# MOTOR_DRIVER.net
KiCad netlist of a schematic drawn in EAGLE
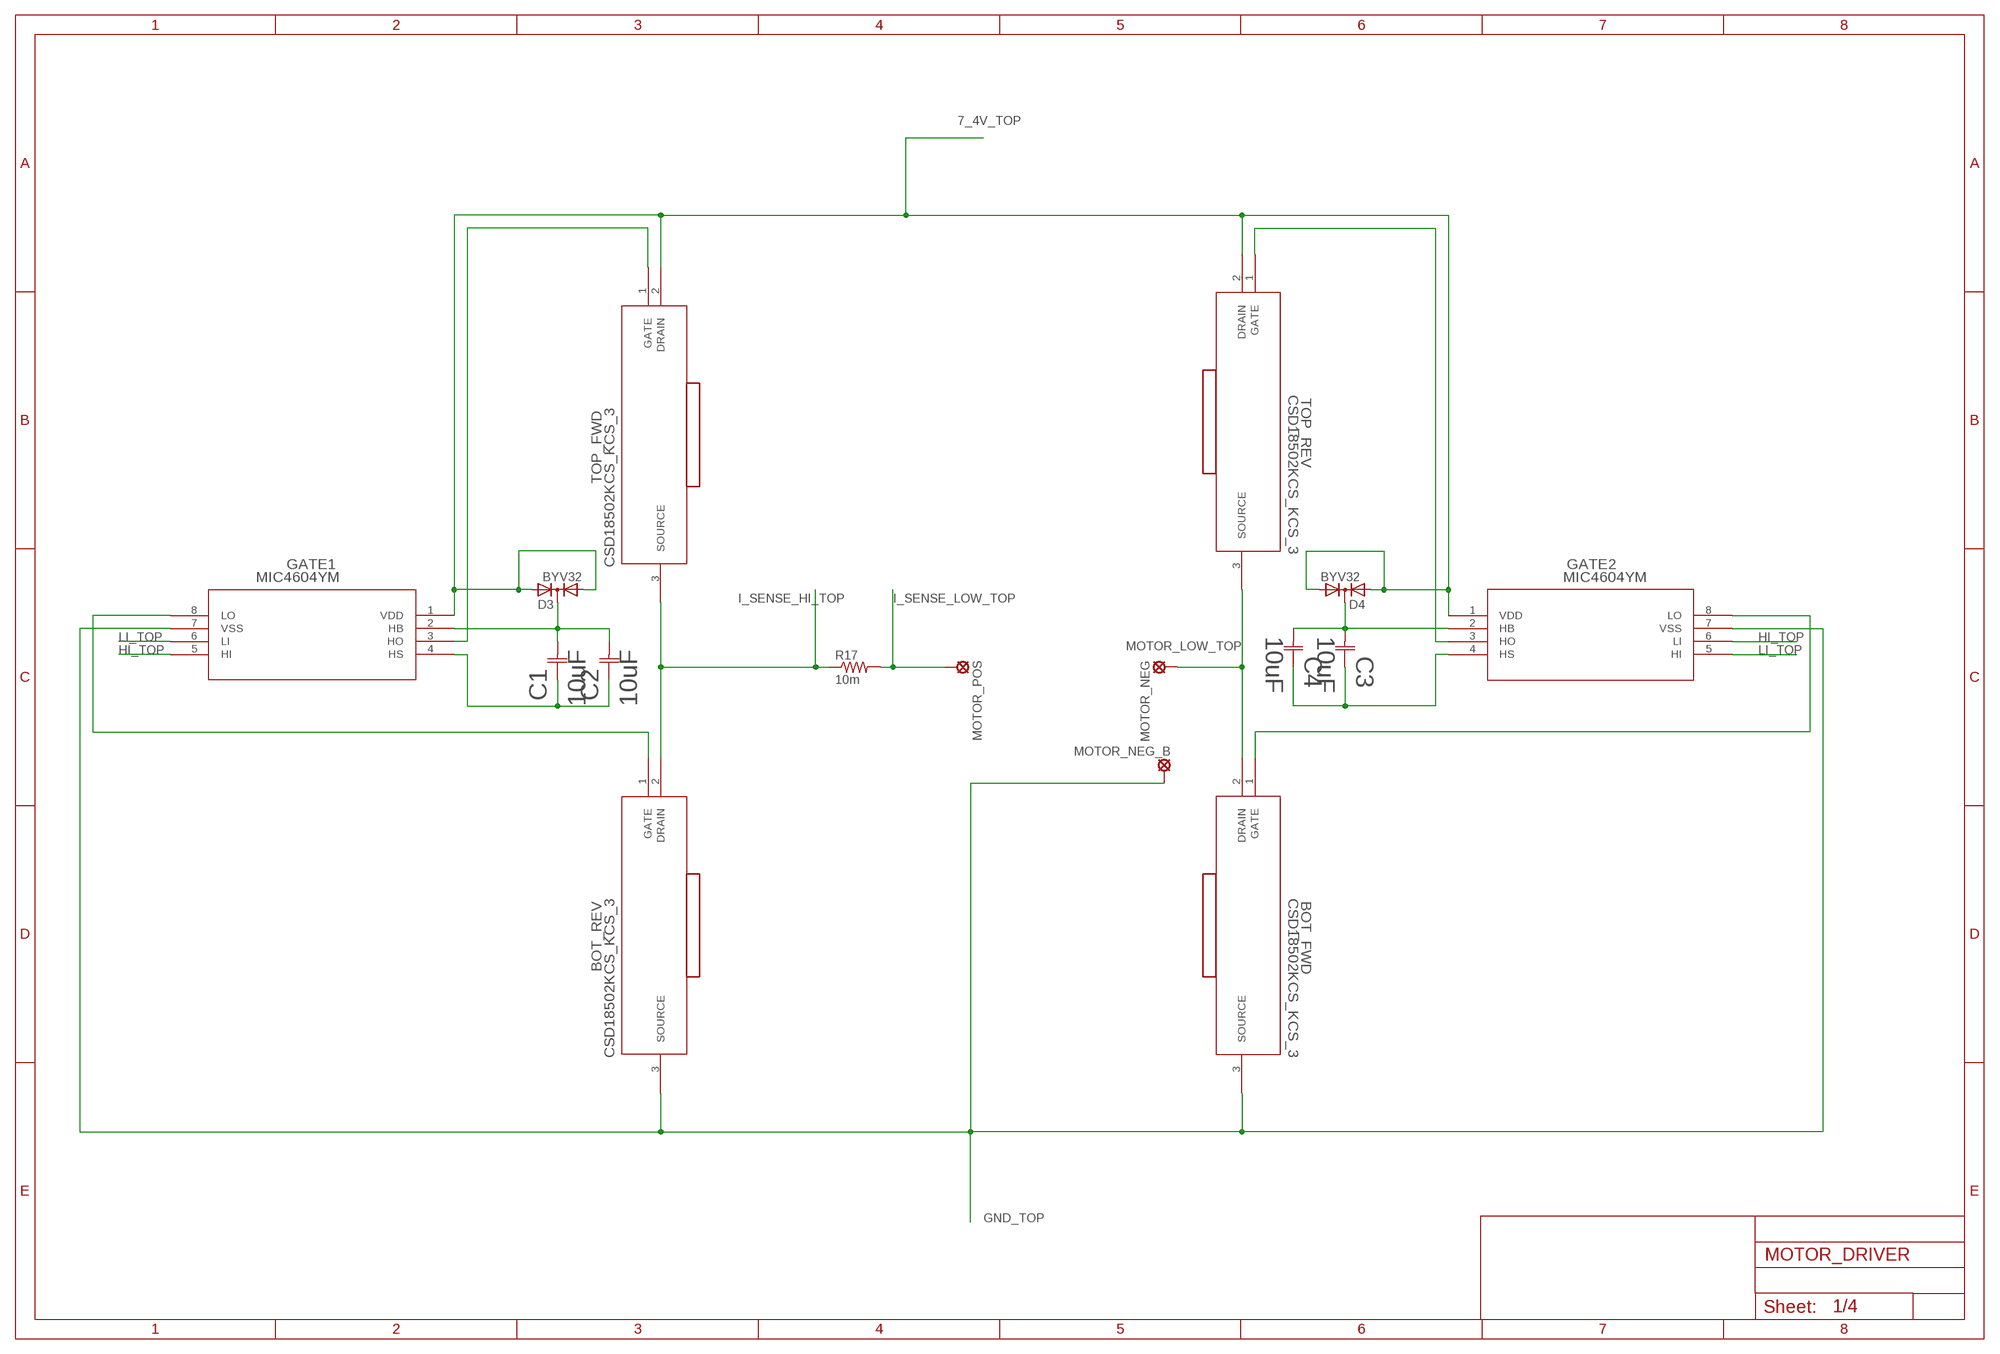
[diagram p0: schematic, sheet 1]
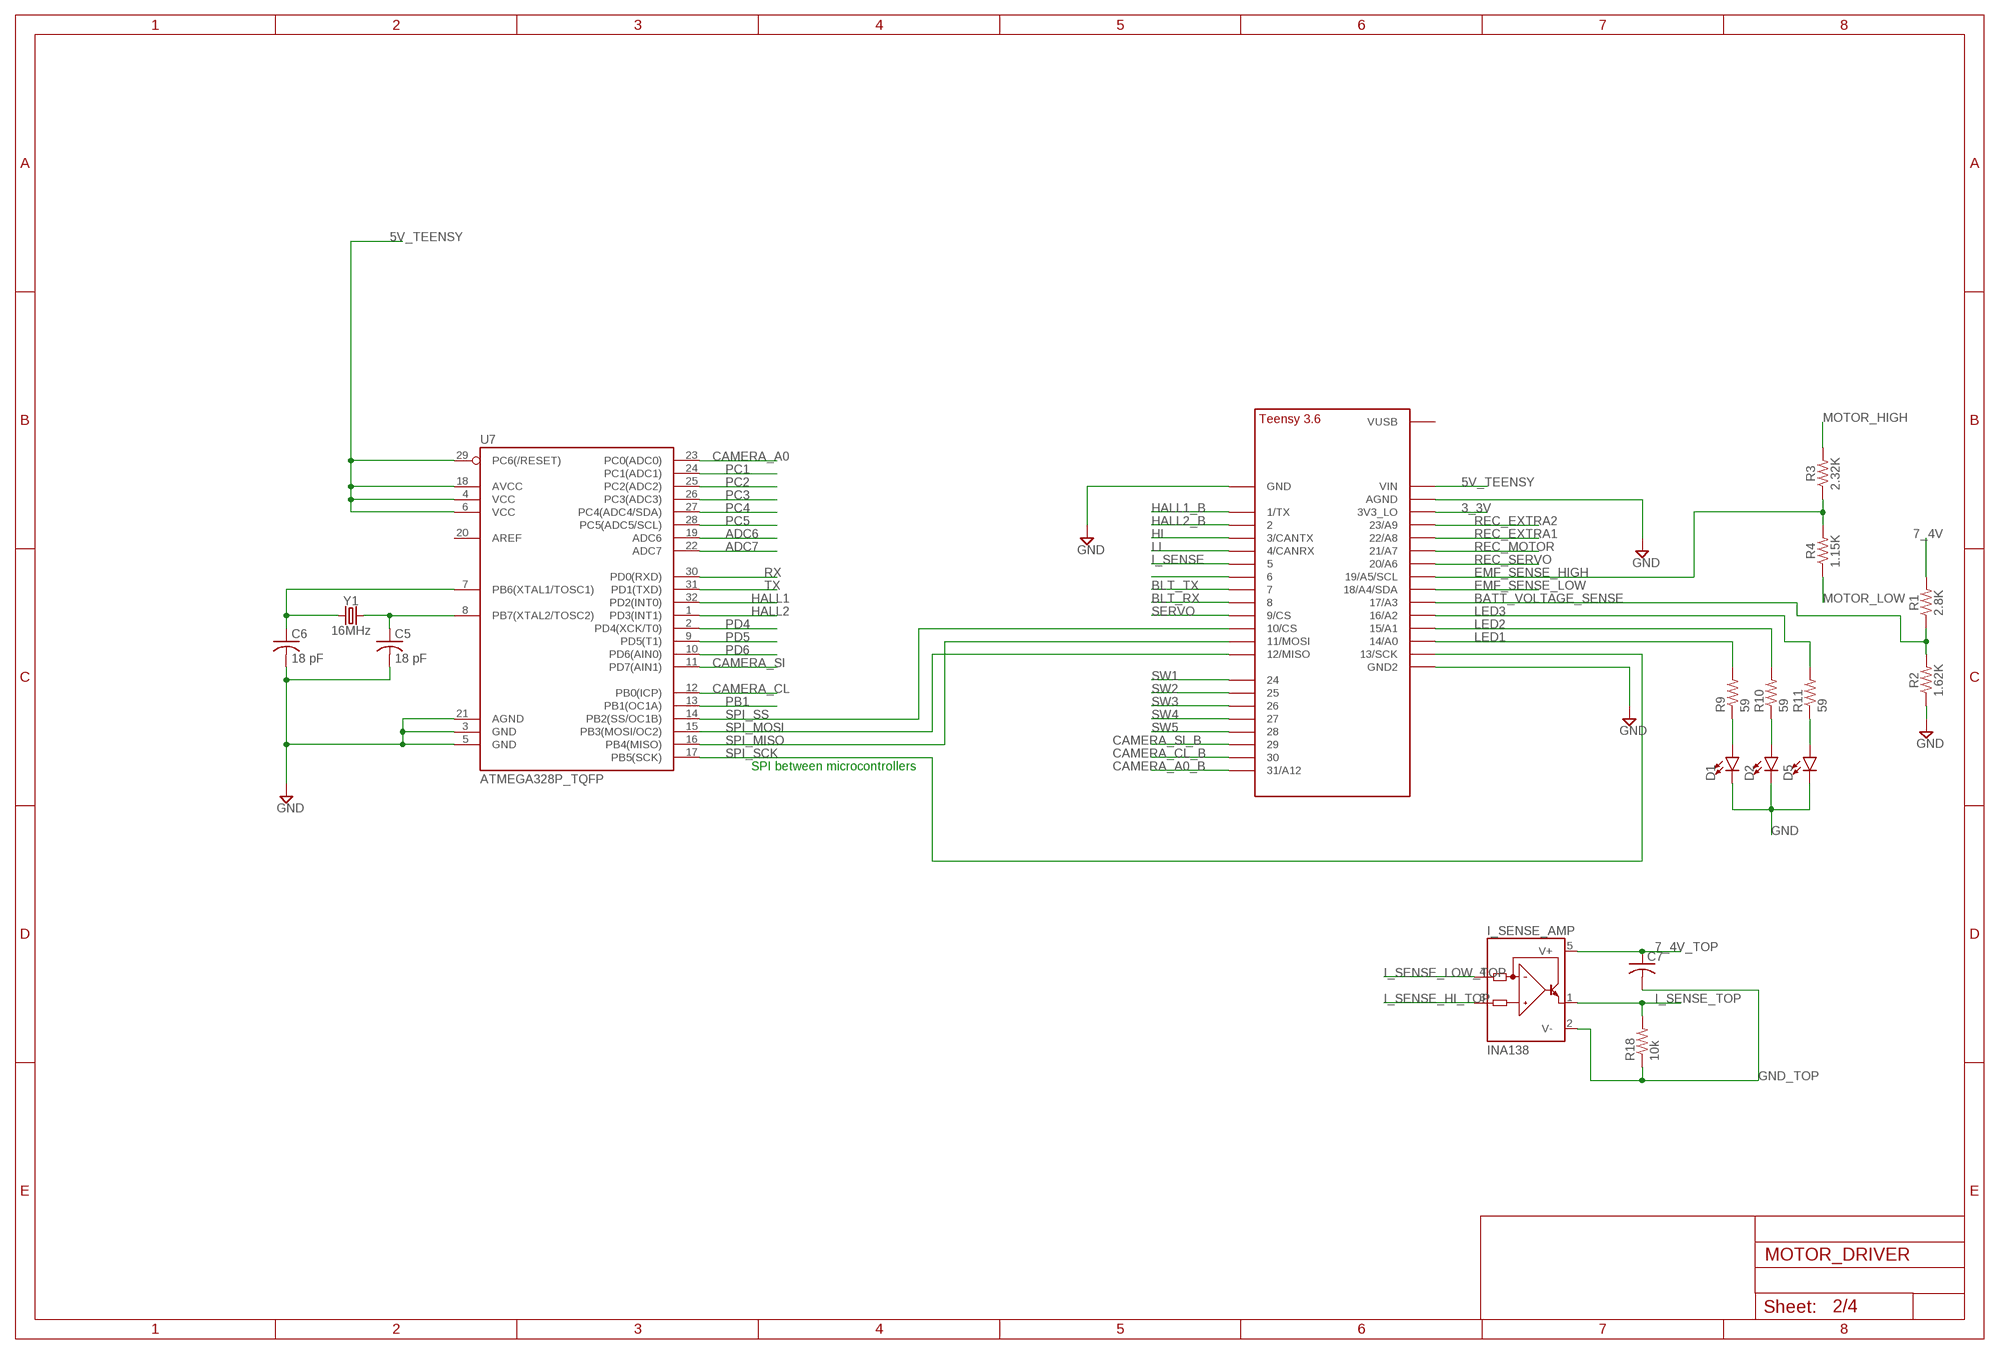
[diagram p1: schematic, sheet 2]
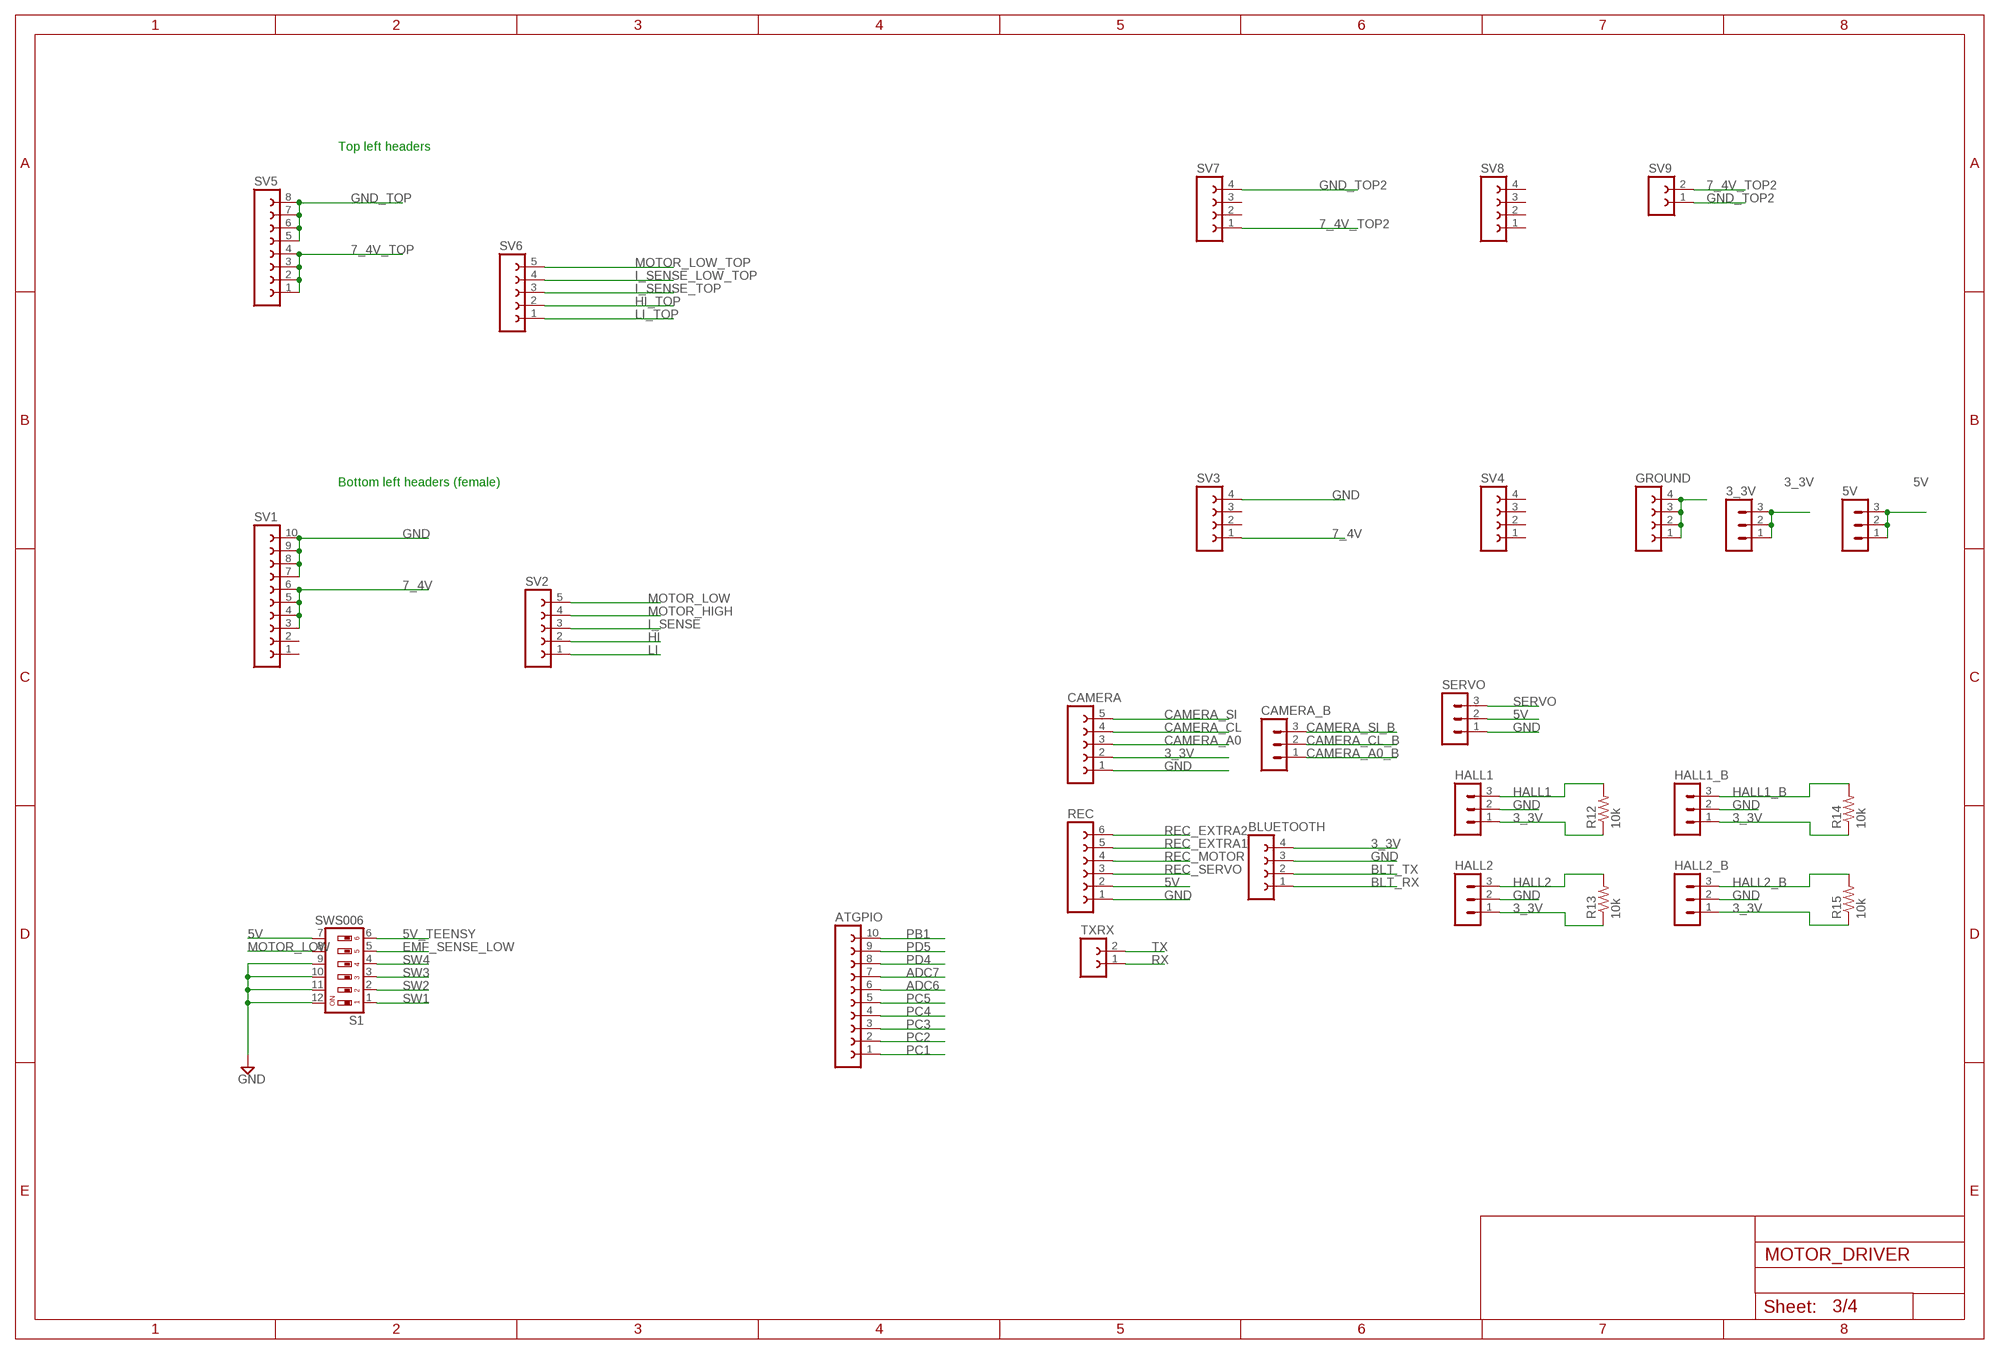
[diagram p2: schematic, sheet 3]
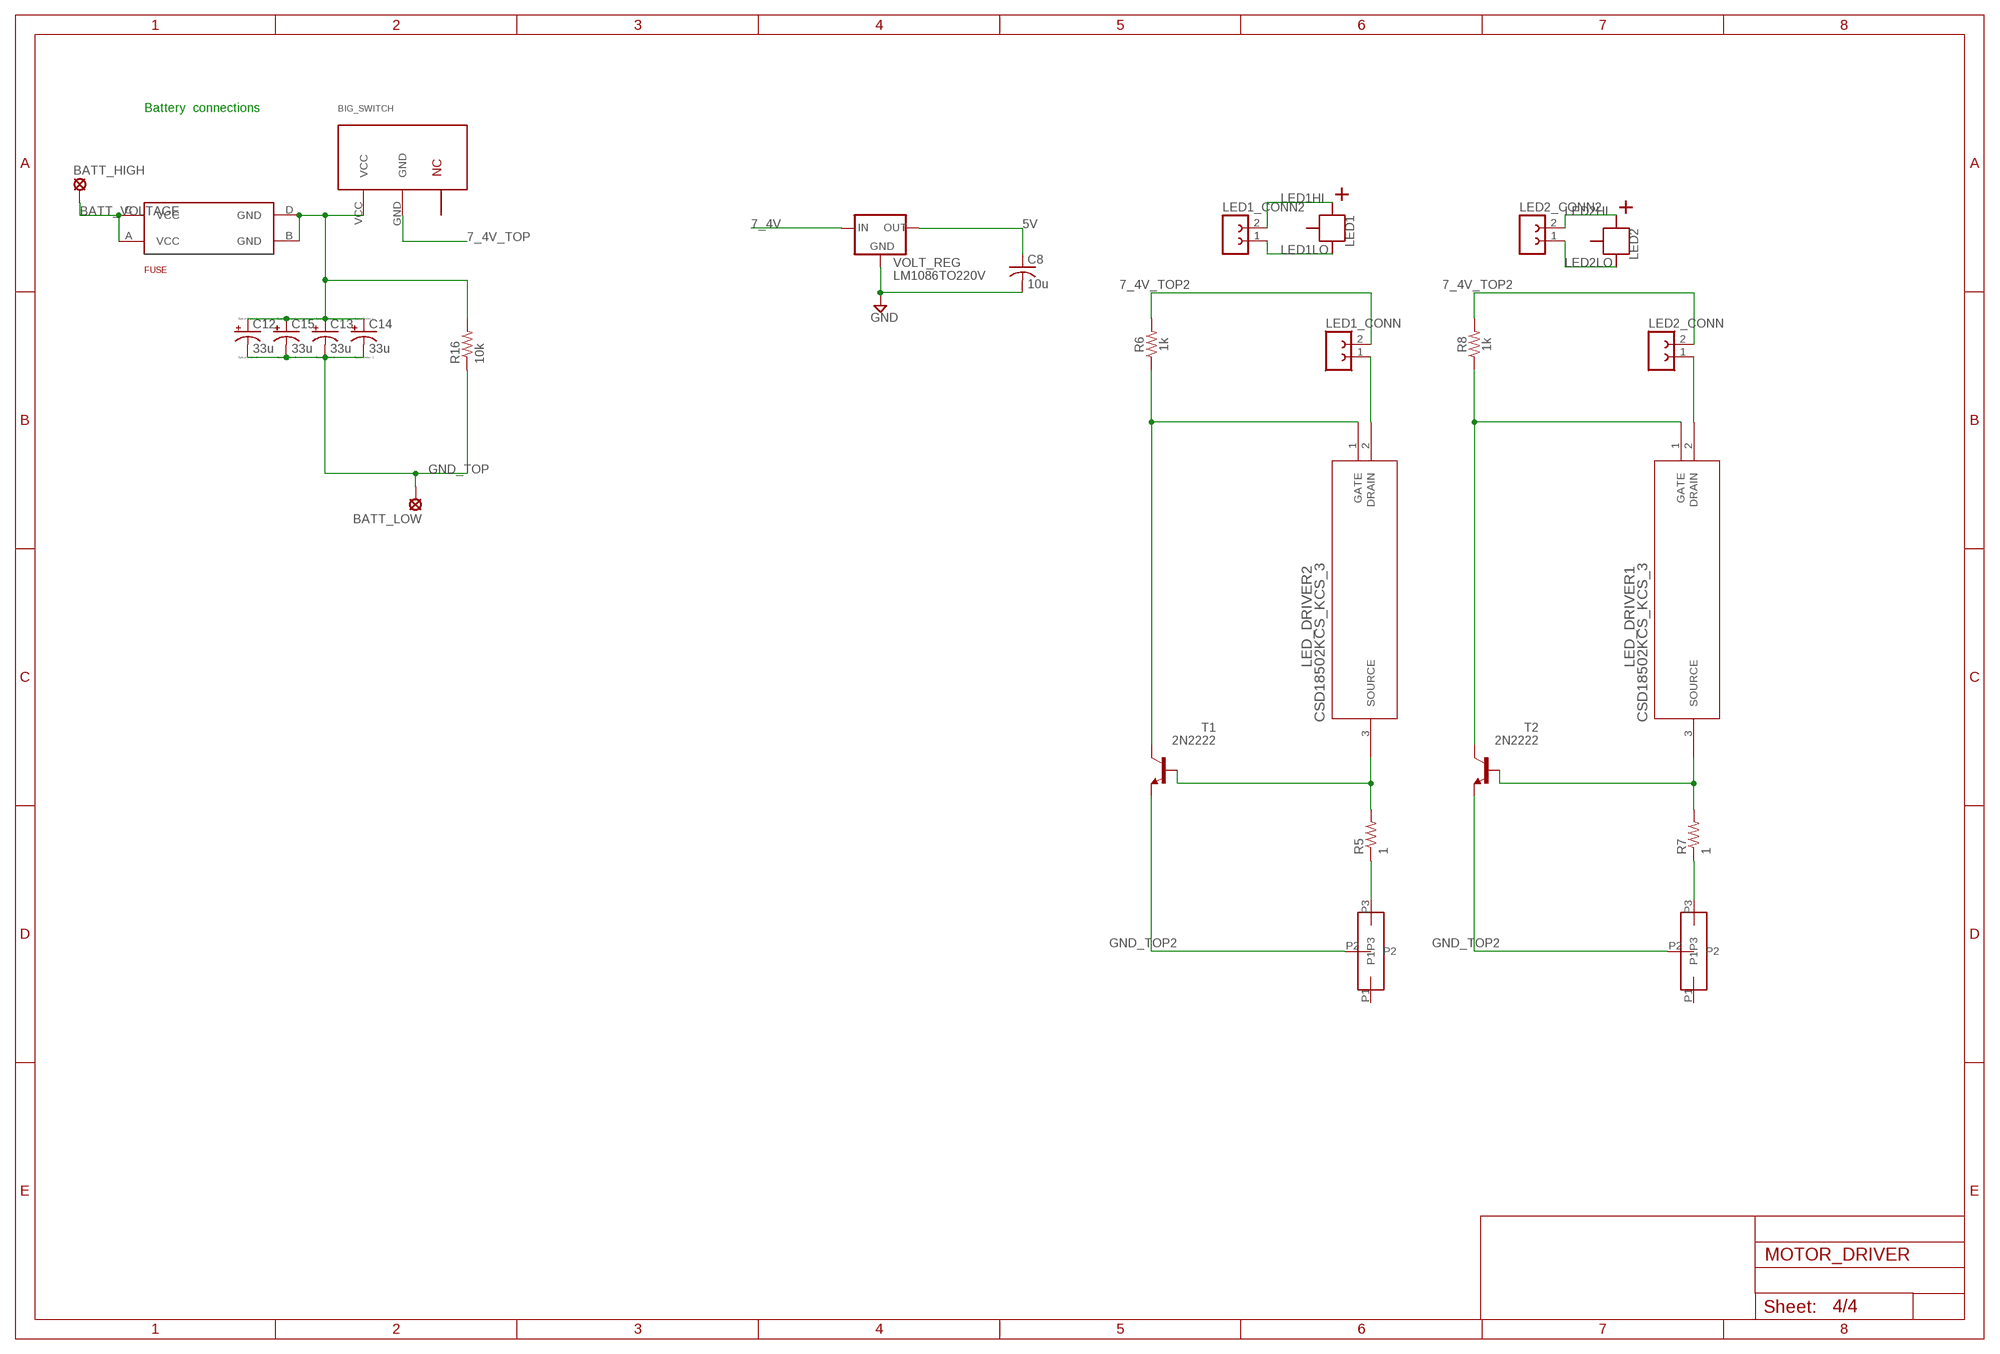
[diagram p3: schematic, sheet 4]

(export (version "E")
  (design (tool "Eeschema 10.0.6"))
  (components
    (comp (ref "BATT_HIGH")
      (value "SE14")
      (footprint "eagle-import:SE14")
      (libsource (lib "eagle-import") (part "SE14"))
    )
    (comp (ref "BATT_LOW")
      (value "SE14")
      (footprint "eagle-import:SE14")
      (libsource (lib "eagle-import") (part "SE14"))
    )
    (comp (ref "BIG_SWITCH")
      (value "BIGSWITCH")
      (footprint "eagle-import:BIGSWITCH")
      (fields
        (field (name "DIGIKEY_PART_NUMBER") "CW106-ND")
        (field (name "MANUFACTURER") "CW Industries")
        (field (name "MANUFACTURER_PART_NUMBER") "GRB238B801BR1")
      )
      (libsource (lib "eagle-import") (part "BIGSWITCH"))
    )
    (comp (ref "C8")
      (value "10u")
      (footprint "eagle-import:C0805")
      (libsource (lib "eagle-import") (part "C-USC0805"))
    )
    (comp (ref "C12")
      (value "33u")
      (footprint "eagle-import:153CLV-1010")
      (libsource (lib "eagle-import") (part "CPOL-US153CLV-1010"))
    )
    (comp (ref "C13")
      (value "33u")
      (footprint "eagle-import:153CLV-1010")
      (libsource (lib "eagle-import") (part "CPOL-US153CLV-1010"))
    )
    (comp (ref "C14")
      (value "33u")
      (footprint "eagle-import:153CLV-1010")
      (libsource (lib "eagle-import") (part "CPOL-US153CLV-1010"))
    )
    (comp (ref "C15")
      (value "33u")
      (footprint "eagle-import:153CLV-1010")
      (libsource (lib "eagle-import") (part "CPOL-US153CLV-1010"))
    )
    (comp (ref "FUSE")
      (value "FUSEHOLDER3588")
      (footprint "eagle-import:FUSEHOLDER3588")
      (fields
        (field (name "DIGIKEY_PART_NUMBER") "F4989-ND")
        (field (name "MANUFACTURER") "Littelfuse Inc.")
        (field (name "MANUFACTURER_PART_NUMBER") "0891010.NXS")
      )
      (libsource (lib "eagle-import") (part "FUSEHOLDER3588"))
    )
    (comp (ref "LED1")
      (value "CREE_XP")
      (footprint "eagle-import:XP")
      (libsource (lib "eagle-import") (part "CREE_XP"))
    )
    (comp (ref "LED1_CONN")
      (value "FE02-1")
      (footprint "eagle-import:FE02-1")
      (libsource (lib "eagle-import") (part "FE02-1"))
    )
    (comp (ref "LED1_CONN2")
      (value "FE02-1")
      (footprint "eagle-import:FE02-1")
      (libsource (lib "eagle-import") (part "FE02-1"))
    )
    (comp (ref "LED2")
      (value "CREE_XP")
      (footprint "eagle-import:XP")
      (libsource (lib "eagle-import") (part "CREE_XP"))
    )
    (comp (ref "LED2_CONN")
      (value "FE02-1")
      (footprint "eagle-import:FE02-1")
      (libsource (lib "eagle-import") (part "FE02-1"))
    )
    (comp (ref "LED2_CONN2")
      (value "FE02-1")
      (footprint "eagle-import:FE02-1")
      (libsource (lib "eagle-import") (part "FE02-1"))
    )
    (comp (ref "LED_DRIVER1")
      (value "CSD18502KCS_KCS_3")
      (footprint "eagle-import:KCS3")
      (fields
        (field (name "DIGIKEY_PART_NUMBER") "296-35013-ND")
        (field (name "MANUFACTURER") "Texas Instruments")
        (field (name "MANUFACTURER_PART_NUMBER") "CSD18533KCS")
      )
      (libsource (lib "eagle-import") (part "CSD18502KCS_KCS_3"))
    )
    (comp (ref "LED_DRIVER2")
      (value "CSD18502KCS_KCS_3")
      (footprint "eagle-import:KCS3")
      (fields
        (field (name "DIGIKEY_PART_NUMBER") "296-35013-ND")
        (field (name "MANUFACTURER") "Texas Instruments")
        (field (name "MANUFACTURER_PART_NUMBER") "CSD18533KCS")
      )
      (libsource (lib "eagle-import") (part "CSD18502KCS_KCS_3"))
    )
    (comp (ref "R5")
      (value "1")
      (footprint "eagle-import:R2512")
      (libsource (lib "eagle-import") (part "R-US_R2512"))
    )
    (comp (ref "R6")
      (value "1k")
      (footprint "eagle-import:AXIAL-0.3")
      (libsource (lib "eagle-import") (part "1KOHM-HORIZ-1/4W-1%"))
    )
    (comp (ref "R7")
      (value "1")
      (footprint "eagle-import:R2512")
      (libsource (lib "eagle-import") (part "R-US_R2512"))
    )
    (comp (ref "R8")
      (value "1k")
      (footprint "eagle-import:AXIAL-0.3")
      (libsource (lib "eagle-import") (part "1KOHM-HORIZ-1/4W-1%"))
    )
    (comp (ref "R16")
      (value "10k")
      (footprint "eagle-import:R0603")
      (libsource (lib "eagle-import") (part "resistor_R-US_R0603"))
    )
    (comp (ref "T1")
      (value "2N2222")
      (footprint "eagle-import:TO18")
      (libsource (lib "eagle-import") (part "2N2222"))
    )
    (comp (ref "T2")
      (value "2N2222")
      (footprint "eagle-import:TO18")
      (libsource (lib "eagle-import") (part "2N2222"))
    )
    (comp (ref "U$3")
      (value "POT")
      (footprint "eagle-import:POT")
      (libsource (lib "eagle-import") (part "POT"))
    )
    (comp (ref "U$7")
      (value "POT")
      (footprint "eagle-import:POT")
      (libsource (lib "eagle-import") (part "POT"))
    )
    (comp (ref "VOLT_REG")
      (value "LM1086TO220V")
      (footprint "eagle-import:TO220S")
      (fields
        (field (name "DIGIKEY_PART_NUMBER") "LM1086IT-5.0/NOPB-ND")
        (field (name "MANUFACTURER") "Texas Instruments")
        (field (name "MANUFACTURER_PART_NUMBER") "LM1086IT-5.0/NOPB")
      )
      (libsource (lib "eagle-import") (part "LM1086TO220V"))
    )
    (comp (ref "3_3V")
      (value "MA03-1")
      (footprint "eagle-import:MA03-1")
      (libsource (lib "eagle-import") (part "MA03-1"))
    )
    (comp (ref "5V")
      (value "MA03-1")
      (footprint "eagle-import:MA03-1")
      (libsource (lib "eagle-import") (part "MA03-1"))
    )
    (comp (ref "ATGPIO")
      (value "FE10-1")
      (footprint "eagle-import:FE10")
      (libsource (lib "eagle-import") (part "FE10-1"))
    )
    (comp (ref "BLUETOOTH")
      (value "FE04-1")
      (footprint "eagle-import:FE04-1")
      (fields
        (field (name "MANUFACTURER") "HC Information Technology")
        (field (name "MANUFACTURER_PART_NUMBER") "HC-06")
      )
      (libsource (lib "eagle-import") (part "FE04-1"))
    )
    (comp (ref "CAMERA")
      (value "FE05-1")
      (footprint "eagle-import:FE05-1")
      (fields
        (field (name "DIGIKEY_PART_NUMBER") "28317-ND")
        (field (name "MANUFACTURER") "Parallax")
        (field (name "MANUFACTURER_PART_NUMBER") "28317")
      )
      (libsource (lib "eagle-import") (part "FE05-1"))
    )
    (comp (ref "CAMERA_B")
      (value "MA03-1")
      (footprint "eagle-import:MA03-1")
      (fields
        (field (name "DIGIKEY_PART_NUMBER") "28317-ND")
        (field (name "MANUFACTURER") "Parallax")
        (field (name "MANUFACTURER_PART_NUMBER") "28317")
      )
      (libsource (lib "eagle-import") (part "MA03-1"))
    )
    (comp (ref "GROUND")
      (value "FE04-1")
      (footprint "eagle-import:FE04-1")
      (libsource (lib "eagle-import") (part "FE04-1"))
    )
    (comp (ref "HALL1")
      (value "MA03-1")
      (footprint "eagle-import:MA03-1")
      (fields
        (field (name "DIGIKEY_PART_NUMBER") "US1881LUA-AAA-000-BU-ND")
        (field (name "MANUFACTURER") "Melexis Technologies NV")
        (field (name "MANUFACTURER_PART_NUMBER") "US1881LUA-AAA-000-BU")
      )
      (libsource (lib "eagle-import") (part "MA03-1"))
    )
    (comp (ref "HALL1_B")
      (value "MA03-1")
      (footprint "eagle-import:MA03-1")
      (fields
        (field (name "DIGIKEY_PART_NUMBER") "US1881LUA-AAA-000-BU-ND")
        (field (name "MANUFACTURER") "Melexis Technologies NV")
        (field (name "MANUFACTURER_PART_NUMBER") "US1881LUA-AAA-000-BU")
      )
      (libsource (lib "eagle-import") (part "MA03-1"))
    )
    (comp (ref "HALL2")
      (value "MA03-1")
      (footprint "eagle-import:MA03-1")
      (fields
        (field (name "DIGIKEY_PART_NUMBER") "US1881LUA-AAA-000-BU-ND")
        (field (name "MANUFACTURER") "Melexis Technologies NV")
        (field (name "MANUFACTURER_PART_NUMBER") "US1881LUA-AAA-000-BU")
      )
      (libsource (lib "eagle-import") (part "MA03-1"))
    )
    (comp (ref "HALL2_B")
      (value "MA03-1")
      (footprint "eagle-import:MA03-1")
      (fields
        (field (name "DIGIKEY_PART_NUMBER") "US1881LUA-AAA-000-BU-ND")
        (field (name "MANUFACTURER") "Melexis Technologies NV")
        (field (name "MANUFACTURER_PART_NUMBER") "US1881LUA-AAA-000-BU")
      )
      (libsource (lib "eagle-import") (part "MA03-1"))
    )
    (comp (ref "R12")
      (value "10k")
      (footprint "eagle-import:R0603")
      (libsource (lib "eagle-import") (part "resistor_R-US_R0603"))
    )
    (comp (ref "R13")
      (value "10k")
      (footprint "eagle-import:R0603")
      (libsource (lib "eagle-import") (part "resistor_R-US_R0603"))
    )
    (comp (ref "R14")
      (value "10k")
      (footprint "eagle-import:R0603")
      (libsource (lib "eagle-import") (part "resistor_R-US_R0603"))
    )
    (comp (ref "R15")
      (value "10k")
      (footprint "eagle-import:R0603")
      (libsource (lib "eagle-import") (part "resistor_R-US_R0603"))
    )
    (comp (ref "REC")
      (value "FE06-1")
      (footprint "eagle-import:FE06")
      (libsource (lib "eagle-import") (part "FE06-1"))
    )
    (comp (ref "S1")
      (value "SWS006")
      (footprint "eagle-import:SMS-006")
      (fields
        (field (name "DIGIKEY_PART_NUMBER") "CT2196MST-ND")
        (field (name "MANUFACTURER") "CTS Electrocomponents")
        (field (name "MANUFACTURER_PART_NUMBER") "219-6MST")
      )
      (libsource (lib "eagle-import") (part "SWS006"))
    )
    (comp (ref "SERVO")
      (value "MA03-1")
      (footprint "eagle-import:MA03-1")
      (fields (field (name "MANUFACTURER") "TrackStar") (field (name "MANUFACTURER_PART_NUMBER") "TS-P12S"))
      (libsource (lib "eagle-import") (part "MA03-1"))
    )
    (comp (ref "SV1")
      (value "FE10-1")
      (footprint "eagle-import:FE10")
      (libsource (lib "eagle-import") (part "FE10-1"))
    )
    (comp (ref "SV2")
      (value "FE05-1")
      (footprint "eagle-import:FE05-1")
      (libsource (lib "eagle-import") (part "FE05-1"))
    )
    (comp (ref "SV3")
      (value "FE04-1")
      (footprint "eagle-import:FE04-1")
      (libsource (lib "eagle-import") (part "FE04-1"))
    )
    (comp (ref "SV4")
      (value "FE04-1")
      (footprint "eagle-import:FE04-1")
      (libsource (lib "eagle-import") (part "FE04-1"))
    )
    (comp (ref "SV5")
      (value "FE08-1")
      (footprint "eagle-import:FE08")
      (libsource (lib "eagle-import") (part "FE08-1"))
    )
    (comp (ref "SV6")
      (value "FE05-1")
      (footprint "eagle-import:FE05-1")
      (libsource (lib "eagle-import") (part "FE05-1"))
    )
    (comp (ref "SV7")
      (value "FE04-1")
      (footprint "eagle-import:FE04-1")
      (libsource (lib "eagle-import") (part "FE04-1"))
    )
    (comp (ref "SV8")
      (value "FE04-1")
      (footprint "eagle-import:FE04-1")
      (libsource (lib "eagle-import") (part "FE04-1"))
    )
    (comp (ref "SV9")
      (value "FE02-1")
      (footprint "eagle-import:FE02-1")
      (libsource (lib "eagle-import") (part "FE02-1"))
    )
    (comp (ref "TXRX")
      (value "FE02-1")
      (footprint "eagle-import:FE02-1")
      (libsource (lib "eagle-import") (part "FE02-1"))
    )
    (comp (ref "BOT_FWD")
      (value "CSD18502KCS_KCS_3")
      (footprint "eagle-import:KCS3")
      (fields
        (field (name "DIGIKEY_PART_NUMBER") "296-35013-ND")
        (field (name "MANUFACTURER") "Texas Instruments")
        (field (name "MANUFACTURER_PART_NUMBER") "CSD18533KCS")
      )
      (libsource (lib "eagle-import") (part "CSD18502KCS_KCS_3"))
    )
    (comp (ref "BOT_REV")
      (value "CSD18502KCS_KCS_3")
      (footprint "eagle-import:KCS3")
      (fields
        (field (name "DIGIKEY_PART_NUMBER") "296-35013-ND")
        (field (name "MANUFACTURER") "Texas Instruments")
        (field (name "MANUFACTURER_PART_NUMBER") "CSD18533KCS")
      )
      (libsource (lib "eagle-import") (part "CSD18502KCS_KCS_3"))
    )
    (comp (ref "C1")
      (value "10uF")
      (footprint "eagle-import:CAP_EEE_B")
      (fields (field (name "MANUFACTURER_PART_NUMBER") "EEE1VA100WR"))
      (libsource (lib "eagle-import") (part "EEE1VA100WR"))
    )
    (comp (ref "C2")
      (value "10uF")
      (footprint "eagle-import:CAP_EEE_B")
      (fields (field (name "MANUFACTURER_PART_NUMBER") "EEE1VA100WR"))
      (libsource (lib "eagle-import") (part "EEE1VA100WR"))
    )
    (comp (ref "C3")
      (value "10uF")
      (footprint "eagle-import:CAP_EEE_B")
      (fields (field (name "MANUFACTURER_PART_NUMBER") "EEE1VA100WR"))
      (libsource (lib "eagle-import") (part "EEE1VA100WR"))
    )
    (comp (ref "C4")
      (value "10uF")
      (footprint "eagle-import:CAP_EEE_B")
      (fields (field (name "MANUFACTURER_PART_NUMBER") "EEE1VA100WR"))
      (libsource (lib "eagle-import") (part "EEE1VA100WR"))
    )
    (comp (ref "D3")
      (value "BYV32")
      (footprint "eagle-import:TO220ABS")
      (libsource (lib "eagle-import") (part "BYV32"))
    )
    (comp (ref "D4")
      (value "BYV32")
      (footprint "eagle-import:TO220ABS")
      (libsource (lib "eagle-import") (part "BYV32"))
    )
    (comp (ref "GATE1")
      (value "MIC4604YM")
      (footprint "eagle-import:SOIC-8_M")
      (fields
        (field (name "DIGIKEY_PART_NUMBER") "576-4395-1-ND")
        (field (name "MANUFACTURER") "Microchip")
        (field (name "MANUFACTURER_PART_NUMBER") "MIC4604YM-T5")
      )
      (libsource (lib "eagle-import") (part "MIC4604YM"))
    )
    (comp (ref "GATE2")
      (value "MIC4604YM")
      (footprint "eagle-import:SOIC-8_M")
      (fields
        (field (name "DIGIKEY_PART_NUMBER") "576-4395-1-ND")
        (field (name "MANUFACTURER") "Microchip")
        (field (name "MANUFACTURER_PART_NUMBER") "MIC4604YM-T5")
      )
      (libsource (lib "eagle-import") (part "MIC4604YM"))
    )
    (comp (ref "MOTOR_NEG")
      (value "SE14")
      (footprint "eagle-import:SE14")
      (libsource (lib "eagle-import") (part "SE14"))
    )
    (comp (ref "MOTOR_NEG_B")
      (value "SE14")
      (footprint "eagle-import:SE14")
      (libsource (lib "eagle-import") (part "SE14"))
    )
    (comp (ref "MOTOR_POS")
      (value "SE14")
      (footprint "eagle-import:SE14")
      (libsource (lib "eagle-import") (part "SE14"))
    )
    (comp (ref "R17")
      (value "10m")
      (footprint "eagle-import:R2512")
      (libsource (lib "eagle-import") (part "R-US_R2512"))
    )
    (comp (ref "TOP_FWD")
      (value "CSD18502KCS_KCS_3")
      (footprint "eagle-import:KCS3")
      (fields
        (field (name "DIGIKEY_PART_NUMBER") "296-35013-ND")
        (field (name "MANUFACTURER") "Texas Instruments")
        (field (name "MANUFACTURER_PART_NUMBER") "CSD18533KCS")
      )
      (libsource (lib "eagle-import") (part "CSD18502KCS_KCS_3"))
    )
    (comp (ref "TOP_REV")
      (value "CSD18502KCS_KCS_3")
      (footprint "eagle-import:KCS3")
      (fields
        (field (name "DIGIKEY_PART_NUMBER") "296-35013-ND")
        (field (name "MANUFACTURER") "Texas Instruments")
        (field (name "MANUFACTURER_PART_NUMBER") "CSD18533KCS")
      )
      (libsource (lib "eagle-import") (part "CSD18502KCS_KCS_3"))
    )
    (comp (ref "U$2")
      (value "HEATSINK")
      (footprint "eagle-import:HEATSINK")
      (fields
        (field (name "DIGIKEY_PART_NUMBER") "HS112-ND")
        (field (name "MANUFACTURER") "Aavid Thermalloy")
        (field (name "MANUFACTURER_PART_NUMBER") "507002B00000G")
      )
      (libsource (lib "eagle-import") (part "HEATSINK"))
    )
    (comp (ref "U$4")
      (value "HEATSINK")
      (footprint "eagle-import:HEATSINK")
      (fields
        (field (name "DIGIKEY_PART_NUMBER") "HS112-ND")
        (field (name "MANUFACTURER") "Aavid Thermalloy")
        (field (name "MANUFACTURER_PART_NUMBER") "507002B00000G")
      )
      (libsource (lib "eagle-import") (part "HEATSINK"))
    )
    (comp (ref "U$5")
      (value "HEATSINK")
      (footprint "eagle-import:HEATSINK")
      (fields
        (field (name "DIGIKEY_PART_NUMBER") "HS112-ND")
        (field (name "MANUFACTURER") "Aavid Thermalloy")
        (field (name "MANUFACTURER_PART_NUMBER") "507002B00000G")
      )
      (libsource (lib "eagle-import") (part "HEATSINK"))
    )
    (comp (ref "U$6")
      (value "HEATSINK")
      (footprint "eagle-import:HEATSINK")
      (fields
        (field (name "DIGIKEY_PART_NUMBER") "HS112-ND")
        (field (name "MANUFACTURER") "Aavid Thermalloy")
        (field (name "MANUFACTURER_PART_NUMBER") "507002B00000G")
      )
      (libsource (lib "eagle-import") (part "HEATSINK"))
    )
    (comp (ref "C5")
      (value "18 pF")
      (footprint "eagle-import:C0603")
      (libsource (lib "eagle-import") (part "C-USC0603"))
    )
    (comp (ref "C6")
      (value "18 pF")
      (footprint "eagle-import:C0603")
      (libsource (lib "eagle-import") (part "C-USC0603"))
    )
    (comp (ref "C7")
      (value "C-USC0603")
      (footprint "eagle-import:C0603")
      (libsource (lib "eagle-import") (part "resistor_C-USC0603"))
    )
    (comp (ref "D1")
      (value "LED0603")
      (footprint "eagle-import:LED-0603")
      (libsource (lib "eagle-import") (part "LED0603"))
    )
    (comp (ref "D2")
      (value "LED0603")
      (footprint "eagle-import:LED-0603")
      (libsource (lib "eagle-import") (part "LED0603"))
    )
    (comp (ref "D5")
      (value "LED0603")
      (footprint "eagle-import:LED-0603")
      (libsource (lib "eagle-import") (part "LED0603"))
    )
    (comp (ref "I_SENSE_AMP")
      (value "INA138")
      (footprint "eagle-import:SOT23-5")
      (fields
        (field (name "DIGIKEY_PART_NUMBER") "INA138NACT-ND")
        (field (name "MANUFACTURER") "Texas Instruments")
        (field (name "MANUFACTURER_PART_NUMBER") "INA138NA/250")
      )
      (libsource (lib "eagle-import") (part "INA138"))
    )
    (comp (ref "R1")
      (value "2.8K")
      (footprint "eagle-import:0805")
      (fields
        (field (name "DIGIKEY_PART_NUMBER") "311-2.80KCRCT-ND")
        (field (name "MANUFACTURER") "Yageo")
        (field (name "MANUFACTURER_PART_NUMBER") "RC0805FR-072K8L")
      )
      (libsource (lib "eagle-import") (part "0.3OHM-0805-1/8W-1%"))
    )
    (comp (ref "R2")
      (value "1.62K")
      (footprint "eagle-import:0805")
      (fields
        (field (name "DIGIKEY_PART_NUMBER") "311-1.62KCRCT-ND")
        (field (name "MANUFACTURER") "Yageo")
        (field (name "MANUFACTURER_PART_NUMBER") "RC0805FR-071K62L")
      )
      (libsource (lib "eagle-import") (part "0.3OHM-0805-1/8W-1%"))
    )
    (comp (ref "R3")
      (value "2.32K")
      (footprint "eagle-import:0805")
      (fields
        (field (name "DIGIKEY_PART_NUMBER") "311-2.32KCRCT-ND")
        (field (name "MANUFACTURER") "Yageo")
        (field (name "MANUFACTURER_PART_NUMBER") "RC0805FR-072K32L")
      )
      (libsource (lib "eagle-import") (part "0.3OHM-0805-1/8W-1%"))
    )
    (comp (ref "R4")
      (value "1.15K")
      (footprint "eagle-import:0805")
      (fields
        (field (name "DIGIKEY_PART_NUMBER") "311-1.15KCRCT-ND")
        (field (name "MANUFACTURER") "Yageo")
        (field (name "MANUFACTURER_PART_NUMBER") "RC0805FR-071K15L")
      )
      (libsource (lib "eagle-import") (part "0.3OHM-0805-1/8W-1%"))
    )
    (comp (ref "R9")
      (value "59")
      (footprint "eagle-import:R0805")
      (libsource (lib "eagle-import") (part "R-US_R0805"))
    )
    (comp (ref "R10")
      (value "59")
      (footprint "eagle-import:R0805")
      (libsource (lib "eagle-import") (part "R-US_R0805"))
    )
    (comp (ref "R11")
      (value "59")
      (footprint "eagle-import:R0805")
      (libsource (lib "eagle-import") (part "R-US_R0805"))
    )
    (comp (ref "R18")
      (value "10k")
      (footprint "eagle-import:R0603")
      (libsource (lib "eagle-import") (part "R-US_R0603"))
    )
    (comp (ref "U$1")
      (value "TEENSY_3.5/3.6_FEWER")
      (footprint "eagle-import:TEENSY_3.5_3.6_BASIC_FEWER_PIN")
      (fields
        (field (name "DIGIKEY_PART_NUMBER") "1568-1443-ND")
        (field (name "MANUFACTURER") "SparkFun Electronics")
        (field (name "MANUFACTURER_PART_NUMBER") "DEV-14055")
      )
      (libsource (lib "eagle-import") (part "TEENSY_3.5/3.6_FEWER"))
    )
    (comp (ref "U7")
      (value "ATMEGA328P_TQFP")
      (footprint "eagle-import:TQFP32-08")
      (fields
        (field (name "DIGIKEY_PART_NUMBER") "ATMEGA328PB-AU-ND")
        (field (name "MANUFACTURER") "Microchip Technology")
        (field (name "MANUFACTURER_PART_NUMBER") "ATMEGA328PB-AU")
      )
      (libsource (lib "eagle-import") (part "ATMEGA328P_TQFP"))
    )
    (comp (ref "Y1")
      (value "16MHz")
      (footprint "eagle-import:HC49US")
      (fields
        (field (name "DIGIKEY_PART_NUMBER") "887-2425-1-ND")
        (field (name "MANUFACTURER") "TXC CORPORATION")
        (field (name "MANUFACTURER_PART_NUMBER") "9C-16.000MBBK-T")
      )
      (libsource (lib "eagle-import") (part "CRYSTAL-16MHZPTH-HC49US"))
    )
  )
  (nets
    (net (code "1") (name "3_3V") (class "Default")
      (node (ref "3_3V") (pin "1") (pinfunction "1_1") (pintype "passive"))
      (node (ref "3_3V") (pin "2") (pinfunction "2_2") (pintype "passive"))
      (node (ref "3_3V") (pin "3") (pinfunction "3_3") (pintype "passive"))
      (node (ref "BLUETOOTH") (pin "4") (pinfunction "4_4") (pintype "passive"))
      (node (ref "CAMERA") (pin "2") (pinfunction "2_2") (pintype "passive"))
      (node (ref "HALL1") (pin "1") (pinfunction "1_1") (pintype "passive"))
      (node (ref "HALL1_B") (pin "1") (pinfunction "1_1") (pintype "passive"))
      (node (ref "HALL2") (pin "1") (pinfunction "1_1") (pintype "passive"))
      (node (ref "HALL2_B") (pin "1") (pinfunction "1_1") (pintype "passive"))
      (node (ref "R12") (pin "1") (pinfunction "1_1") (pintype "passive"))
      (node (ref "R13") (pin "1") (pinfunction "1_1") (pintype "passive"))
      (node (ref "R14") (pin "1") (pinfunction "1_1") (pintype "passive"))
      (node (ref "R15") (pin "1") (pinfunction "1_1") (pintype "passive"))
      (node (ref "U$1") (pin "3V3_LO") (pinfunction "3V3_LO_3V3_LO") (pintype "bidirectional"))
    )
    (net (code "2") (name "5V") (class "Default")
      (node (ref "5V") (pin "1") (pinfunction "1_1") (pintype "passive"))
      (node (ref "5V") (pin "2") (pinfunction "2_2") (pintype "passive"))
      (node (ref "5V") (pin "3") (pinfunction "3_3") (pintype "passive"))
      (node (ref "C8") (pin "1") (pinfunction "1_1") (pintype "passive"))
      (node (ref "REC") (pin "2") (pinfunction "2_2") (pintype "passive"))
      (node (ref "S1") (pin "7") (pinfunction "7_7") (pintype "passive"))
      (node (ref "SERVO") (pin "2") (pinfunction "2_2") (pintype "passive"))
      (node (ref "VOLT_REG") (pin "2") (pinfunction "OUT_2") (pintype "passive"))
    )
    (net (code "3") (name "5V_TEENSY") (class "Default")
      (node (ref "S1") (pin "6") (pinfunction "6_6") (pintype "passive"))
      (node (ref "U$1") (pin "VIN") (pinfunction "VIN_VIN") (pintype "bidirectional"))
      (node (ref "U7") (pin "18") (pinfunction "AVCC_18") (pintype "bidirectional"))
      (node (ref "U7") (pin "29") (pinfunction "PC6(/RESET)_29") (pintype "bidirectional"))
      (node (ref "U7") (pin "4") (pinfunction "VCC_4") (pintype "bidirectional"))
      (node (ref "U7") (pin "6") (pinfunction "VCC_6") (pintype "bidirectional"))
    )
    (net (code "4") (name "7_4V") (class "Default")
      (node (ref "R1") (pin "2") (pinfunction "2_2") (pintype "passive"))
      (node (ref "SV1") (pin "3") (pinfunction "3_3") (pintype "passive"))
      (node (ref "SV1") (pin "4") (pinfunction "4_4") (pintype "passive"))
      (node (ref "SV1") (pin "5") (pinfunction "5_5") (pintype "passive"))
      (node (ref "SV1") (pin "6") (pinfunction "6_6") (pintype "passive"))
      (node (ref "SV3") (pin "1") (pinfunction "1_1") (pintype "passive"))
      (node (ref "VOLT_REG") (pin "3") (pinfunction "IN_3") (pintype "input"))
    )
    (net (code "5") (name "7_4V_TOP") (class "Default")
      (node (ref "BIG_SWITCH") (pin "GND") (pinfunction "GND_GND") (pintype "power_in"))
      (node (ref "C7") (pin "1") (pinfunction "1_1") (pintype "passive"))
      (node (ref "D3") (pin "A1") (pinfunction "A1_A1") (pintype "passive"))
      (node (ref "D3") (pin "A2") (pinfunction "A2_A2") (pintype "passive"))
      (node (ref "D4") (pin "A1") (pinfunction "A1_A1") (pintype "passive"))
      (node (ref "D4") (pin "A2") (pinfunction "A2_A2") (pintype "passive"))
      (node (ref "GATE1") (pin "1") (pinfunction "VDD_1") (pintype "power_in"))
      (node (ref "GATE2") (pin "1") (pinfunction "VDD_1") (pintype "power_in"))
      (node (ref "I_SENSE_AMP") (pin "5") (pinfunction "V+_5") (pintype "power_in"))
      (node (ref "SV5") (pin "1") (pinfunction "1_1") (pintype "passive"))
      (node (ref "SV5") (pin "2") (pinfunction "2_2") (pintype "passive"))
      (node (ref "SV5") (pin "3") (pinfunction "3_3") (pintype "passive"))
      (node (ref "SV5") (pin "4") (pinfunction "4_4") (pintype "passive"))
      (node (ref "TOP_FWD") (pin "2") (pinfunction "DRAIN_2") (pintype "passive"))
      (node (ref "TOP_REV") (pin "2") (pinfunction "DRAIN_2") (pintype "passive"))
    )
    (net (code "6") (name "7_4V_TOP2") (class "Default")
      (node (ref "LED1_CONN") (pin "2") (pinfunction "2_2") (pintype "passive"))
      (node (ref "LED2_CONN") (pin "2") (pinfunction "2_2") (pintype "passive"))
      (node (ref "R6") (pin "P$2") (pinfunction "2_P$2") (pintype "passive"))
      (node (ref "R8") (pin "P$2") (pinfunction "2_P$2") (pintype "passive"))
      (node (ref "SV7") (pin "1") (pinfunction "1_1") (pintype "passive"))
      (node (ref "SV9") (pin "2") (pinfunction "2_2") (pintype "passive"))
    )
    (net (code "7") (name "ADC6") (class "Default")
      (node (ref "ATGPIO") (pin "6") (pinfunction "6_6") (pintype "passive"))
      (node (ref "U7") (pin "19") (pinfunction "ADC6_19") (pintype "bidirectional"))
    )
    (net (code "8") (name "ADC7") (class "Default")
      (node (ref "ATGPIO") (pin "7") (pinfunction "7_7") (pintype "passive"))
      (node (ref "U7") (pin "22") (pinfunction "ADC7_22") (pintype "bidirectional"))
    )
    (net (code "9") (name "BATT_VOLTAGE") (class "Default")
      (node (ref "BATT_HIGH") (pin "MP") (pinfunction "MP_MP") (pintype "passive"))
      (node (ref "FUSE") (pin "A") (pinfunction "VCC_A") (pintype "power_in"))
      (node (ref "FUSE") (pin "C") (pinfunction "VCC_C") (pintype "power_in"))
    )
    (net (code "10") (name "BATT_VOLTAGE_SENSE") (class "Default")
      (node (ref "R1") (pin "1") (pinfunction "1_1") (pintype "passive"))
      (node (ref "R2") (pin "2") (pinfunction "2_2") (pintype "passive"))
      (node (ref "U$1") (pin "17/A3") (pinfunction "17/A3_17/A3") (pintype "bidirectional"))
    )
    (net (code "11") (name "BLT_RX") (class "Default")
      (node (ref "BLUETOOTH") (pin "1") (pinfunction "1_1") (pintype "passive"))
      (node (ref "U$1") (pin "8") (pinfunction "8_8") (pintype "bidirectional"))
    )
    (net (code "12") (name "BLT_TX") (class "Default")
      (node (ref "BLUETOOTH") (pin "2") (pinfunction "2_2") (pintype "passive"))
      (node (ref "U$1") (pin "7") (pinfunction "7_7") (pintype "bidirectional"))
    )
    (net (code "13") (name "CAMERA_A0") (class "Default")
      (node (ref "CAMERA") (pin "3") (pinfunction "3_3") (pintype "passive"))
      (node (ref "U7") (pin "23") (pinfunction "PC0(ADC0)_23") (pintype "bidirectional"))
    )
    (net (code "14") (name "CAMERA_A0_B") (class "Default")
      (node (ref "CAMERA_B") (pin "1") (pinfunction "1_1") (pintype "passive"))
      (node (ref "U$1") (pin "31/A12") (pinfunction "31/A12_31/A12") (pintype "bidirectional"))
    )
    (net (code "15") (name "CAMERA_CL") (class "Default")
      (node (ref "CAMERA") (pin "4") (pinfunction "4_4") (pintype "passive"))
      (node (ref "U7") (pin "12") (pinfunction "PB0(ICP)_12") (pintype "bidirectional"))
    )
    (net (code "16") (name "CAMERA_CL_B") (class "Default")
      (node (ref "CAMERA_B") (pin "2") (pinfunction "2_2") (pintype "passive"))
      (node (ref "U$1") (pin "30") (pinfunction "30_30") (pintype "bidirectional"))
    )
    (net (code "17") (name "CAMERA_SI") (class "Default")
      (node (ref "CAMERA") (pin "5") (pinfunction "5_5") (pintype "passive"))
      (node (ref "U7") (pin "11") (pinfunction "PD7(AIN1)_11") (pintype "bidirectional"))
    )
    (net (code "18") (name "CAMERA_SI_B") (class "Default")
      (node (ref "CAMERA_B") (pin "3") (pinfunction "3_3") (pintype "passive"))
      (node (ref "U$1") (pin "29") (pinfunction "29_29") (pintype "bidirectional"))
    )
    (net (code "19") (name "EMF_SENSE_HIGH") (class "Default")
      (node (ref "R3") (pin "1") (pinfunction "1_1") (pintype "passive"))
      (node (ref "R4") (pin "2") (pinfunction "2_2") (pintype "passive"))
      (node (ref "U$1") (pin "19/A5/SCL") (pinfunction "19/A5/SCL_19/A5/SCL") (pintype "bidirectional"))
    )
    (net (code "20") (name "EMF_SENSE_LOW") (class "Default")
      (node (ref "S1") (pin "5") (pinfunction "5_5") (pintype "passive"))
      (node (ref "U$1") (pin "18/A4/SDA") (pinfunction "18/A4/SDA_18/A4/SDA") (pintype "bidirectional"))
    )
    (net (code "21") (name "GND") (class "Default")
      (node (ref "BLUETOOTH") (pin "3") (pinfunction "3_3") (pintype "passive"))
      (node (ref "C5") (pin "2") (pinfunction "2_2") (pintype "passive"))
      (node (ref "C6") (pin "2") (pinfunction "2_2") (pintype "passive"))
      (node (ref "C8") (pin "2") (pinfunction "2_2") (pintype "passive"))
      (node (ref "CAMERA") (pin "1") (pinfunction "1_1") (pintype "passive"))
      (node (ref "D1") (pin "C") (pinfunction "C_C") (pintype "passive"))
      (node (ref "D2") (pin "C") (pinfunction "C_C") (pintype "passive"))
      (node (ref "D5") (pin "C") (pinfunction "C_C") (pintype "passive"))
      (node (ref "GROUND") (pin "1") (pinfunction "1_1") (pintype "passive"))
      (node (ref "GROUND") (pin "2") (pinfunction "2_2") (pintype "passive"))
      (node (ref "GROUND") (pin "3") (pinfunction "3_3") (pintype "passive"))
      (node (ref "GROUND") (pin "4") (pinfunction "4_4") (pintype "passive"))
      (node (ref "HALL1") (pin "2") (pinfunction "2_2") (pintype "passive"))
      (node (ref "HALL1_B") (pin "2") (pinfunction "2_2") (pintype "passive"))
      (node (ref "HALL2") (pin "2") (pinfunction "2_2") (pintype "passive"))
      (node (ref "HALL2_B") (pin "2") (pinfunction "2_2") (pintype "passive"))
      (node (ref "R2") (pin "1") (pinfunction "1_1") (pintype "passive"))
      (node (ref "REC") (pin "1") (pinfunction "1_1") (pintype "passive"))
      (node (ref "S1") (pin "10") (pinfunction "10_10") (pintype "passive"))
      (node (ref "S1") (pin "11") (pinfunction "11_11") (pintype "passive"))
      (node (ref "S1") (pin "12") (pinfunction "12_12") (pintype "passive"))
      (node (ref "S1") (pin "9") (pinfunction "9_9") (pintype "passive"))
      (node (ref "SERVO") (pin "1") (pinfunction "1_1") (pintype "passive"))
      (node (ref "SV1") (pin "10") (pinfunction "10_10") (pintype "passive"))
      (node (ref "SV1") (pin "7") (pinfunction "7_7") (pintype "passive"))
      (node (ref "SV1") (pin "8") (pinfunction "8_8") (pintype "passive"))
      (node (ref "SV1") (pin "9") (pinfunction "9_9") (pintype "passive"))
      (node (ref "SV3") (pin "4") (pinfunction "4_4") (pintype "passive"))
      (node (ref "U$1") (pin "AGND") (pinfunction "AGND_AGND") (pintype "bidirectional"))
      (node (ref "U$1") (pin "GND") (pinfunction "GND_GND") (pintype "bidirectional"))
      (node (ref "U$1") (pin "GND2") (pinfunction "GND2_GND2") (pintype "bidirectional"))
      (node (ref "U7") (pin "21") (pinfunction "AGND_21") (pintype "bidirectional"))
      (node (ref "U7") (pin "3") (pinfunction "GND_3") (pintype "bidirectional"))
      (node (ref "U7") (pin "5") (pinfunction "GND_5") (pintype "bidirectional"))
      (node (ref "VOLT_REG") (pin "1") (pinfunction "GND_1") (pintype "input"))
    )
    (net (code "22") (name "GND_TOP") (class "Default")
      (node (ref "BATT_LOW") (pin "MP") (pinfunction "MP_MP") (pintype "passive"))
      (node (ref "BOT_FWD") (pin "3") (pinfunction "SOURCE_3") (pintype "passive"))
      (node (ref "BOT_REV") (pin "3") (pinfunction "SOURCE_3") (pintype "passive"))
      (node (ref "C12") (pin "-") (pinfunction "-_-") (pintype "passive"))
      (node (ref "C13") (pin "-") (pinfunction "-_-") (pintype "passive"))
      (node (ref "C14") (pin "-") (pinfunction "-_-") (pintype "passive"))
      (node (ref "C15") (pin "-") (pinfunction "-_-") (pintype "passive"))
      (node (ref "C7") (pin "2") (pinfunction "2_2") (pintype "passive"))
      (node (ref "GATE1") (pin "7") (pinfunction "VSS_7") (pintype "power_in"))
      (node (ref "GATE2") (pin "7") (pinfunction "VSS_7") (pintype "power_in"))
      (node (ref "I_SENSE_AMP") (pin "2") (pinfunction "V-_2") (pintype "power_in"))
      (node (ref "MOTOR_NEG_B") (pin "MP") (pinfunction "MP_MP") (pintype "passive"))
      (node (ref "R16") (pin "1") (pinfunction "1_1") (pintype "passive"))
      (node (ref "R18") (pin "1") (pinfunction "1_1") (pintype "passive"))
      (node (ref "SV5") (pin "5") (pinfunction "5_5") (pintype "passive"))
      (node (ref "SV5") (pin "6") (pinfunction "6_6") (pintype "passive"))
      (node (ref "SV5") (pin "7") (pinfunction "7_7") (pintype "passive"))
      (node (ref "SV5") (pin "8") (pinfunction "8_8") (pintype "passive"))
    )
    (net (code "23") (name "GND_TOP2") (class "Default")
      (node (ref "SV7") (pin "4") (pinfunction "4_4") (pintype "passive"))
      (node (ref "SV9") (pin "1") (pinfunction "1_1") (pintype "passive"))
      (node (ref "T1") (pin "1") (pinfunction "E_1") (pintype "passive"))
      (node (ref "T2") (pin "1") (pinfunction "E_1") (pintype "passive"))
      (node (ref "U$3") (pin "P2") (pinfunction "P2_P2") (pintype "bidirectional"))
      (node (ref "U$7") (pin "P2") (pinfunction "P2_P2") (pintype "bidirectional"))
    )
    (net (code "24") (name "HALL1") (class "Default")
      (node (ref "HALL1") (pin "3") (pinfunction "3_3") (pintype "passive"))
      (node (ref "R12") (pin "2") (pinfunction "2_2") (pintype "passive"))
      (node (ref "U7") (pin "32") (pinfunction "PD2(INT0)_32") (pintype "bidirectional"))
    )
    (net (code "25") (name "HALL1_B") (class "Default")
      (node (ref "HALL1_B") (pin "3") (pinfunction "3_3") (pintype "passive"))
      (node (ref "R14") (pin "2") (pinfunction "2_2") (pintype "passive"))
      (node (ref "U$1") (pin "1/TX") (pinfunction "1/TX_1/TX") (pintype "bidirectional"))
    )
    (net (code "26") (name "HALL2") (class "Default")
      (node (ref "HALL2") (pin "3") (pinfunction "3_3") (pintype "passive"))
      (node (ref "R13") (pin "2") (pinfunction "2_2") (pintype "passive"))
      (node (ref "U7") (pin "1") (pinfunction "PD3(INT1)_1") (pintype "bidirectional"))
    )
    (net (code "27") (name "HALL2_B") (class "Default")
      (node (ref "HALL2_B") (pin "3") (pinfunction "3_3") (pintype "passive"))
      (node (ref "R15") (pin "2") (pinfunction "2_2") (pintype "passive"))
      (node (ref "U$1") (pin "2") (pinfunction "2_2") (pintype "bidirectional"))
    )
    (net (code "28") (name "HI") (class "Default")
      (node (ref "SV2") (pin "2") (pinfunction "2_2") (pintype "passive"))
      (node (ref "U$1") (pin "3/CANTX") (pinfunction "3/CANTX_3/CANTX") (pintype "bidirectional"))
    )
    (net (code "29") (name "HI_TOP") (class "Default")
      (node (ref "GATE1") (pin "5") (pinfunction "HI_5") (pintype "input"))
      (node (ref "GATE2") (pin "6") (pinfunction "LI_6") (pintype "input"))
      (node (ref "SV6") (pin "2") (pinfunction "2_2") (pintype "passive"))
    )
    (net (code "30") (name "I_SENSE") (class "Default")
      (node (ref "SV2") (pin "3") (pinfunction "3_3") (pintype "passive"))
      (node (ref "U$1") (pin "5") (pinfunction "5_5") (pintype "bidirectional"))
    )
    (net (code "31") (name "I_SENSE_HI_TOP") (class "Default")
      (node (ref "BOT_REV") (pin "2") (pinfunction "DRAIN_2") (pintype "passive"))
      (node (ref "I_SENSE_AMP") (pin "3") (pinfunction "IN+_3") (pintype "input"))
      (node (ref "R17") (pin "1") (pinfunction "1_1") (pintype "passive"))
      (node (ref "TOP_FWD") (pin "3") (pinfunction "SOURCE_3") (pintype "passive"))
    )
    (net (code "32") (name "I_SENSE_LOW_TOP") (class "Default")
      (node (ref "I_SENSE_AMP") (pin "4") (pinfunction "IN-_4") (pintype "input"))
      (node (ref "MOTOR_POS") (pin "MP") (pinfunction "MP_MP") (pintype "passive"))
      (node (ref "R17") (pin "2") (pinfunction "2_2") (pintype "passive"))
      (node (ref "SV6") (pin "4") (pinfunction "4_4") (pintype "passive"))
    )
    (net (code "33") (name "I_SENSE_TOP") (class "Default")
      (node (ref "I_SENSE_AMP") (pin "1") (pinfunction "OUT_1") (pintype "output"))
      (node (ref "R18") (pin "2") (pinfunction "2_2") (pintype "passive"))
      (node (ref "SV6") (pin "3") (pinfunction "3_3") (pintype "passive"))
    )
    (net (code "34") (name "LED1") (class "Default")
      (node (ref "R9") (pin "2") (pinfunction "2_2") (pintype "passive"))
      (node (ref "U$1") (pin "14/A0") (pinfunction "14/A0_14/A0") (pintype "bidirectional"))
    )
    (net (code "35") (name "LED1HI") (class "Default")
      (node (ref "LED1") (pin "POSITIVE") (pinfunction "POSITIVE_POSITIVE") (pintype "bidirectional"))
      (node (ref "LED1") (pin "POSITIVE1") (pinfunction "POSITIVE_POSITIVE1") (pintype "bidirectional"))
      (node (ref "LED1_CONN2") (pin "2") (pinfunction "2_2") (pintype "passive"))
    )
    (net (code "36") (name "LED1LO") (class "Default")
      (node (ref "LED1") (pin "NEGATIVE") (pinfunction "NEGATIVE_NEGATIVE") (pintype "bidirectional"))
      (node (ref "LED1") (pin "NEGATIVE1") (pinfunction "NEGATIVE_NEGATIVE1") (pintype "bidirectional"))
      (node (ref "LED1_CONN2") (pin "1") (pinfunction "1_1") (pintype "passive"))
    )
    (net (code "37") (name "LED2") (class "Default")
      (node (ref "R10") (pin "2") (pinfunction "2_2") (pintype "passive"))
      (node (ref "U$1") (pin "15/A1") (pinfunction "15/A1_15/A1") (pintype "bidirectional"))
    )
    (net (code "38") (name "LED2HI") (class "Default")
      (node (ref "LED2") (pin "POSITIVE") (pinfunction "POSITIVE_POSITIVE") (pintype "bidirectional"))
      (node (ref "LED2") (pin "POSITIVE1") (pinfunction "POSITIVE_POSITIVE1") (pintype "bidirectional"))
      (node (ref "LED2_CONN2") (pin "2") (pinfunction "2_2") (pintype "passive"))
    )
    (net (code "39") (name "LED2LO") (class "Default")
      (node (ref "LED2") (pin "NEGATIVE") (pinfunction "NEGATIVE_NEGATIVE") (pintype "bidirectional"))
      (node (ref "LED2") (pin "NEGATIVE1") (pinfunction "NEGATIVE_NEGATIVE1") (pintype "bidirectional"))
      (node (ref "LED2_CONN2") (pin "1") (pinfunction "1_1") (pintype "passive"))
    )
    (net (code "40") (name "LED3") (class "Default")
      (node (ref "R11") (pin "2") (pinfunction "2_2") (pintype "passive"))
      (node (ref "U$1") (pin "16/A2") (pinfunction "16/A2_16/A2") (pintype "bidirectional"))
    )
    (net (code "41") (name "LI") (class "Default")
      (node (ref "SV2") (pin "1") (pinfunction "1_1") (pintype "passive"))
      (node (ref "U$1") (pin "4/CANRX") (pinfunction "4/CANRX_4/CANRX") (pintype "bidirectional"))
    )
    (net (code "42") (name "LI_TOP") (class "Default")
      (node (ref "GATE1") (pin "6") (pinfunction "LI_6") (pintype "input"))
      (node (ref "GATE2") (pin "5") (pinfunction "HI_5") (pintype "input"))
      (node (ref "SV6") (pin "1") (pinfunction "1_1") (pintype "passive"))
    )
    (net (code "43") (name "MOTOR_HIGH") (class "Default")
      (node (ref "R3") (pin "2") (pinfunction "2_2") (pintype "passive"))
      (node (ref "SV2") (pin "4") (pinfunction "4_4") (pintype "passive"))
    )
    (net (code "44") (name "MOTOR_LOW") (class "Default")
      (node (ref "R4") (pin "1") (pinfunction "1_1") (pintype "passive"))
      (node (ref "S1") (pin "8") (pinfunction "8_8") (pintype "passive"))
      (node (ref "SV2") (pin "5") (pinfunction "5_5") (pintype "passive"))
    )
    (net (code "45") (name "MOTOR_LOW_TOP") (class "Default")
      (node (ref "BOT_FWD") (pin "2") (pinfunction "DRAIN_2") (pintype "passive"))
      (node (ref "MOTOR_NEG") (pin "MP") (pinfunction "MP_MP") (pintype "passive"))
      (node (ref "SV6") (pin "5") (pinfunction "5_5") (pintype "passive"))
      (node (ref "TOP_REV") (pin "3") (pinfunction "SOURCE_3") (pintype "passive"))
    )
    (net (code "46") (name "Net-(BIG_SWITCH-PadVCC)") (class "Default")
      (node (ref "BIG_SWITCH") (pin "VCC") (pinfunction "VCC_VCC") (pintype "power_in"))
      (node (ref "C12") (pin "+") (pinfunction "+_+") (pintype "passive"))
      (node (ref "C13") (pin "+") (pinfunction "+_+") (pintype "passive"))
      (node (ref "C14") (pin "+") (pinfunction "+_+") (pintype "passive"))
      (node (ref "C15") (pin "+") (pinfunction "+_+") (pintype "passive"))
      (node (ref "FUSE") (pin "B") (pinfunction "GND_B") (pintype "power_in"))
      (node (ref "FUSE") (pin "D") (pinfunction "GND_D") (pintype "power_in"))
      (node (ref "R16") (pin "2") (pinfunction "2_2") (pintype "passive"))
    )
    (net (code "47") (name "Net-(BOT_FWD-GATE)") (class "Default")
      (node (ref "BOT_FWD") (pin "1") (pinfunction "GATE_1") (pintype "passive"))
      (node (ref "GATE2") (pin "8") (pinfunction "LO_8") (pintype "output"))
    )
    (net (code "48") (name "Net-(BOT_REV-GATE)") (class "Default")
      (node (ref "BOT_REV") (pin "1") (pinfunction "GATE_1") (pintype "passive"))
      (node (ref "GATE1") (pin "8") (pinfunction "LO_8") (pintype "output"))
    )
    (net (code "49") (name "Net-(D1-PadA)") (class "Default")
      (node (ref "D1") (pin "A") (pinfunction "A_A") (pintype "passive"))
      (node (ref "R9") (pin "1") (pinfunction "1_1") (pintype "passive"))
    )
    (net (code "50") (name "Net-(D2-PadA)") (class "Default")
      (node (ref "D2") (pin "A") (pinfunction "A_A") (pintype "passive"))
      (node (ref "R10") (pin "1") (pinfunction "1_1") (pintype "passive"))
    )
    (net (code "51") (name "Net-(D5-PadA)") (class "Default")
      (node (ref "D5") (pin "A") (pinfunction "A_A") (pintype "passive"))
      (node (ref "R11") (pin "1") (pinfunction "1_1") (pintype "passive"))
    )
    (net (code "52") (name "Net-(GATE1-HB)") (class "Default")
      (node (ref "C1") (pin "2") (pinfunction "2_2") (pintype "passive"))
      (node (ref "C2") (pin "2") (pinfunction "2_2") (pintype "passive"))
      (node (ref "D3") (pin "C") (pinfunction "C_C") (pintype "passive"))
      (node (ref "GATE1") (pin "2") (pinfunction "HB_2") (pintype "passive"))
    )
    (net (code "53") (name "Net-(GATE1-HO)") (class "Default")
      (node (ref "GATE1") (pin "3") (pinfunction "HO_3") (pintype "output"))
      (node (ref "TOP_FWD") (pin "1") (pinfunction "GATE_1") (pintype "passive"))
    )
    (net (code "54") (name "Net-(GATE1-HS)") (class "Default")
      (node (ref "C1") (pin "1") (pinfunction "1_1") (pintype "passive"))
      (node (ref "C2") (pin "1") (pinfunction "1_1") (pintype "passive"))
      (node (ref "GATE1") (pin "4") (pinfunction "HS_4") (pintype "passive"))
    )
    (net (code "55") (name "Net-(GATE2-HB)") (class "Default")
      (node (ref "C3") (pin "2") (pinfunction "2_2") (pintype "passive"))
      (node (ref "C4") (pin "2") (pinfunction "2_2") (pintype "passive"))
      (node (ref "D4") (pin "C") (pinfunction "C_C") (pintype "passive"))
      (node (ref "GATE2") (pin "2") (pinfunction "HB_2") (pintype "passive"))
    )
    (net (code "56") (name "Net-(GATE2-HO)") (class "Default")
      (node (ref "GATE2") (pin "3") (pinfunction "HO_3") (pintype "output"))
      (node (ref "TOP_REV") (pin "1") (pinfunction "GATE_1") (pintype "passive"))
    )
    (net (code "57") (name "Net-(GATE2-HS)") (class "Default")
      (node (ref "C3") (pin "1") (pinfunction "1_1") (pintype "passive"))
      (node (ref "C4") (pin "1") (pinfunction "1_1") (pintype "passive"))
      (node (ref "GATE2") (pin "4") (pinfunction "HS_4") (pintype "passive"))
    )
    (net (code "58") (name "Net-(LED_DRIVER1-DRAIN)") (class "Default")
      (node (ref "LED2_CONN") (pin "1") (pinfunction "1_1") (pintype "passive"))
      (node (ref "LED_DRIVER1") (pin "2") (pinfunction "DRAIN_2") (pintype "passive"))
    )
    (net (code "59") (name "Net-(LED_DRIVER1-GATE)") (class "Default")
      (node (ref "LED_DRIVER1") (pin "1") (pinfunction "GATE_1") (pintype "passive"))
      (node (ref "R8") (pin "P$1") (pinfunction "1_P$1") (pintype "passive"))
      (node (ref "T2") (pin "3") (pinfunction "C_3") (pintype "passive"))
    )
    (net (code "60") (name "Net-(LED_DRIVER1-SOURCE)") (class "Default")
      (node (ref "LED_DRIVER1") (pin "3") (pinfunction "SOURCE_3") (pintype "passive"))
      (node (ref "R7") (pin "2") (pinfunction "2_2") (pintype "passive"))
      (node (ref "T2") (pin "2") (pinfunction "B_2") (pintype "passive"))
    )
    (net (code "61") (name "Net-(LED_DRIVER2-DRAIN)") (class "Default")
      (node (ref "LED1_CONN") (pin "1") (pinfunction "1_1") (pintype "passive"))
      (node (ref "LED_DRIVER2") (pin "2") (pinfunction "DRAIN_2") (pintype "passive"))
    )
    (net (code "62") (name "Net-(LED_DRIVER2-GATE)") (class "Default")
      (node (ref "LED_DRIVER2") (pin "1") (pinfunction "GATE_1") (pintype "passive"))
      (node (ref "R6") (pin "P$1") (pinfunction "1_P$1") (pintype "passive"))
      (node (ref "T1") (pin "3") (pinfunction "C_3") (pintype "passive"))
    )
    (net (code "63") (name "Net-(LED_DRIVER2-SOURCE)") (class "Default")
      (node (ref "LED_DRIVER2") (pin "3") (pinfunction "SOURCE_3") (pintype "passive"))
      (node (ref "R5") (pin "2") (pinfunction "2_2") (pintype "passive"))
      (node (ref "T1") (pin "2") (pinfunction "B_2") (pintype "passive"))
    )
    (net (code "64") (name "Net-(R5-Pad1)") (class "Default")
      (node (ref "R5") (pin "1") (pinfunction "1_1") (pintype "passive"))
      (node (ref "U$7") (pin "P3") (pinfunction "P3_P3") (pintype "bidirectional"))
    )
    (net (code "65") (name "Net-(R7-Pad1)") (class "Default")
      (node (ref "R7") (pin "1") (pinfunction "1_1") (pintype "passive"))
      (node (ref "U$3") (pin "P3") (pinfunction "P3_P3") (pintype "bidirectional"))
    )
    (net (code "66") (name "Net-(U7-PB6(XTAL1{slash}TOSC1))") (class "Default")
      (node (ref "C6") (pin "1") (pinfunction "1_1") (pintype "passive"))
      (node (ref "U7") (pin "7") (pinfunction "PB6(XTAL1/TOSC1)_7") (pintype "bidirectional"))
      (node (ref "Y1") (pin "1") (pinfunction "1_1") (pintype "passive"))
    )
    (net (code "67") (name "Net-(U7-PB7(XTAL2{slash}TOSC2))") (class "Default")
      (node (ref "C5") (pin "1") (pinfunction "1_1") (pintype "passive"))
      (node (ref "U7") (pin "8") (pinfunction "PB7(XTAL2/TOSC2)_8") (pintype "bidirectional"))
      (node (ref "Y1") (pin "2") (pinfunction "2_2") (pintype "passive"))
    )
    (net (code "68") (name "PB1") (class "Default")
      (node (ref "ATGPIO") (pin "10") (pinfunction "10_10") (pintype "passive"))
      (node (ref "U7") (pin "13") (pinfunction "PB1(OC1A)_13") (pintype "bidirectional"))
    )
    (net (code "69") (name "PC1") (class "Default")
      (node (ref "ATGPIO") (pin "1") (pinfunction "1_1") (pintype "passive"))
      (node (ref "U7") (pin "24") (pinfunction "PC1(ADC1)_24") (pintype "bidirectional"))
    )
    (net (code "70") (name "PC2") (class "Default")
      (node (ref "ATGPIO") (pin "2") (pinfunction "2_2") (pintype "passive"))
      (node (ref "U7") (pin "25") (pinfunction "PC2(ADC2)_25") (pintype "bidirectional"))
    )
    (net (code "71") (name "PC3") (class "Default")
      (node (ref "ATGPIO") (pin "3") (pinfunction "3_3") (pintype "passive"))
      (node (ref "U7") (pin "26") (pinfunction "PC3(ADC3)_26") (pintype "bidirectional"))
    )
    (net (code "72") (name "PC4") (class "Default")
      (node (ref "ATGPIO") (pin "4") (pinfunction "4_4") (pintype "passive"))
      (node (ref "U7") (pin "27") (pinfunction "PC4(ADC4/SDA)_27") (pintype "bidirectional"))
    )
    (net (code "73") (name "PC5") (class "Default")
      (node (ref "ATGPIO") (pin "5") (pinfunction "5_5") (pintype "passive"))
      (node (ref "U7") (pin "28") (pinfunction "PC5(ADC5/SCL)_28") (pintype "bidirectional"))
    )
    (net (code "74") (name "PD4") (class "Default")
      (node (ref "ATGPIO") (pin "8") (pinfunction "8_8") (pintype "passive"))
      (node (ref "U7") (pin "2") (pinfunction "PD4(XCK/T0)_2") (pintype "bidirectional"))
    )
    (net (code "75") (name "PD5") (class "Default")
      (node (ref "ATGPIO") (pin "9") (pinfunction "9_9") (pintype "passive"))
      (node (ref "U7") (pin "9") (pinfunction "PD5(T1)_9") (pintype "bidirectional"))
    )
    (net (code "76") (name "PD6") (class "Default")
      (node (ref "U7") (pin "10") (pinfunction "PD6(AIN0)_10") (pintype "bidirectional"))
    )
    (net (code "77") (name "REC_EXTRA1") (class "Default")
      (node (ref "REC") (pin "5") (pinfunction "5_5") (pintype "passive"))
      (node (ref "U$1") (pin "22/A8") (pinfunction "22/A8_22/A8") (pintype "bidirectional"))
    )
    (net (code "78") (name "REC_EXTRA2") (class "Default")
      (node (ref "REC") (pin "6") (pinfunction "6_6") (pintype "passive"))
      (node (ref "U$1") (pin "23/A9") (pinfunction "23/A9_23/A9") (pintype "bidirectional"))
    )
    (net (code "79") (name "REC_MOTOR") (class "Default")
      (node (ref "REC") (pin "4") (pinfunction "4_4") (pintype "passive"))
      (node (ref "U$1") (pin "21/A7") (pinfunction "21/A7_21/A7") (pintype "bidirectional"))
    )
    (net (code "80") (name "REC_SERVO") (class "Default")
      (node (ref "REC") (pin "3") (pinfunction "3_3") (pintype "passive"))
      (node (ref "U$1") (pin "20/A6") (pinfunction "20/A6_20/A6") (pintype "bidirectional"))
    )
    (net (code "81") (name "RX") (class "Default")
      (node (ref "TXRX") (pin "1") (pinfunction "1_1") (pintype "passive"))
      (node (ref "U7") (pin "30") (pinfunction "PD0(RXD)_30") (pintype "bidirectional"))
    )
    (net (code "82") (name "SERVO") (class "Default")
      (node (ref "SERVO") (pin "3") (pinfunction "3_3") (pintype "passive"))
      (node (ref "U$1") (pin "9/CS") (pinfunction "9/CS_9/CS") (pintype "bidirectional"))
    )
    (net (code "83") (name "SPI_MISO") (class "Default")
      (node (ref "U$1") (pin "11/MOSI") (pinfunction "11/MOSI_11/MOSI") (pintype "bidirectional"))
      (node (ref "U7") (pin "16") (pinfunction "PB4(MISO)_16") (pintype "bidirectional"))
    )
    (net (code "84") (name "SPI_MOSI") (class "Default")
      (node (ref "U$1") (pin "12/MISO") (pinfunction "12/MISO_12/MISO") (pintype "bidirectional"))
      (node (ref "U7") (pin "15") (pinfunction "PB3(MOSI/OC2)_15") (pintype "bidirectional"))
    )
    (net (code "85") (name "SPI_SCK") (class "Default")
      (node (ref "U$1") (pin "13/SCK") (pinfunction "13/SCK_13/SCK") (pintype "bidirectional"))
      (node (ref "U7") (pin "17") (pinfunction "PB5(SCK)_17") (pintype "bidirectional"))
    )
    (net (code "86") (name "SPI_SS") (class "Default")
      (node (ref "U$1") (pin "10/CS") (pinfunction "10/CS_10/CS") (pintype "bidirectional"))
      (node (ref "U7") (pin "14") (pinfunction "PB2(SS/OC1B)_14") (pintype "bidirectional"))
    )
    (net (code "87") (name "SW1") (class "Default")
      (node (ref "S1") (pin "1") (pinfunction "1_1") (pintype "passive"))
      (node (ref "U$1") (pin "24") (pinfunction "24_24") (pintype "bidirectional"))
    )
    (net (code "88") (name "SW2") (class "Default")
      (node (ref "S1") (pin "2") (pinfunction "2_2") (pintype "passive"))
      (node (ref "U$1") (pin "25") (pinfunction "25_25") (pintype "bidirectional"))
    )
    (net (code "89") (name "SW3") (class "Default")
      (node (ref "S1") (pin "3") (pinfunction "3_3") (pintype "passive"))
      (node (ref "U$1") (pin "26") (pinfunction "26_26") (pintype "bidirectional"))
    )
    (net (code "90") (name "SW4") (class "Default")
      (node (ref "S1") (pin "4") (pinfunction "4_4") (pintype "passive"))
      (node (ref "U$1") (pin "27") (pinfunction "27_27") (pintype "bidirectional"))
    )
    (net (code "91") (name "SW5") (class "Default")
      (node (ref "U$1") (pin "28") (pinfunction "28_28") (pintype "bidirectional"))
    )
    (net (code "92") (name "TX") (class "Default")
      (node (ref "TXRX") (pin "2") (pinfunction "2_2") (pintype "passive"))
      (node (ref "U7") (pin "31") (pinfunction "PD1(TXD)_31") (pintype "bidirectional"))
    )
    (net (code "93") (name "unconnected-(LED1-PadTHERMAL)") (class "Default")
      (node (ref "LED1") (pin "THERMAL") (pinfunction "THERMAL_THERMAL") (pintype "bidirectional"))
    )
    (net (code "94") (name "unconnected-(LED2-PadTHERMAL)") (class "Default")
      (node (ref "LED2") (pin "THERMAL") (pinfunction "THERMAL_THERMAL") (pintype "bidirectional"))
    )
    (net (code "95") (name "unconnected-(SV1-Pad1)") (class "Default")
      (node (ref "SV1") (pin "1") (pinfunction "1_1") (pintype "passive"))
    )
    (net (code "96") (name "unconnected-(SV1-Pad2)") (class "Default")
      (node (ref "SV1") (pin "2") (pinfunction "2_2") (pintype "passive"))
    )
    (net (code "97") (name "unconnected-(SV3-Pad2)") (class "Default")
      (node (ref "SV3") (pin "2") (pinfunction "2_2") (pintype "passive"))
    )
    (net (code "98") (name "unconnected-(SV3-Pad3)") (class "Default")
      (node (ref "SV3") (pin "3") (pinfunction "3_3") (pintype "passive"))
    )
    (net (code "99") (name "unconnected-(SV4-Pad1)") (class "Default")
      (node (ref "SV4") (pin "1") (pinfunction "1_1") (pintype "passive"))
    )
    (net (code "100") (name "unconnected-(SV4-Pad2)") (class "Default")
      (node (ref "SV4") (pin "2") (pinfunction "2_2") (pintype "passive"))
    )
    (net (code "101") (name "unconnected-(SV4-Pad3)") (class "Default")
      (node (ref "SV4") (pin "3") (pinfunction "3_3") (pintype "passive"))
    )
    (net (code "102") (name "unconnected-(SV4-Pad4)") (class "Default")
      (node (ref "SV4") (pin "4") (pinfunction "4_4") (pintype "passive"))
    )
    (net (code "103") (name "unconnected-(SV7-Pad2)") (class "Default")
      (node (ref "SV7") (pin "2") (pinfunction "2_2") (pintype "passive"))
    )
    (net (code "104") (name "unconnected-(SV7-Pad3)") (class "Default")
      (node (ref "SV7") (pin "3") (pinfunction "3_3") (pintype "passive"))
    )
    (net (code "105") (name "unconnected-(SV8-Pad1)") (class "Default")
      (node (ref "SV8") (pin "1") (pinfunction "1_1") (pintype "passive"))
    )
    (net (code "106") (name "unconnected-(SV8-Pad2)") (class "Default")
      (node (ref "SV8") (pin "2") (pinfunction "2_2") (pintype "passive"))
    )
    (net (code "107") (name "unconnected-(SV8-Pad3)") (class "Default")
      (node (ref "SV8") (pin "3") (pinfunction "3_3") (pintype "passive"))
    )
    (net (code "108") (name "unconnected-(SV8-Pad4)") (class "Default")
      (node (ref "SV8") (pin "4") (pinfunction "4_4") (pintype "passive"))
    )
    (net (code "109") (name "unconnected-(U$1-Pad6)") (class "Default")
      (node (ref "U$1") (pin "6") (pinfunction "6_6") (pintype "bidirectional"))
    )
    (net (code "110") (name "unconnected-(U$1-PadVUSB)") (class "Default")
      (node (ref "U$1") (pin "VUSB") (pinfunction "VUSB_VUSB") (pintype "bidirectional"))
    )
    (net (code "111") (name "unconnected-(U$3-PadP1)") (class "Default")
      (node (ref "U$3") (pin "P1") (pinfunction "P1_P1") (pintype "bidirectional"))
    )
    (net (code "112") (name "unconnected-(U$7-PadP1)") (class "Default")
      (node (ref "U$7") (pin "P1") (pinfunction "P1_P1") (pintype "bidirectional"))
    )
    (net (code "113") (name "unconnected-(U7-AREF-Pad20)") (class "Default")
      (node (ref "U7") (pin "20") (pinfunction "AREF_20") (pintype "bidirectional"))
    )
  )
)
